# touchy_feely.net
KiCad netlist of a schematic drawn in EAGLE
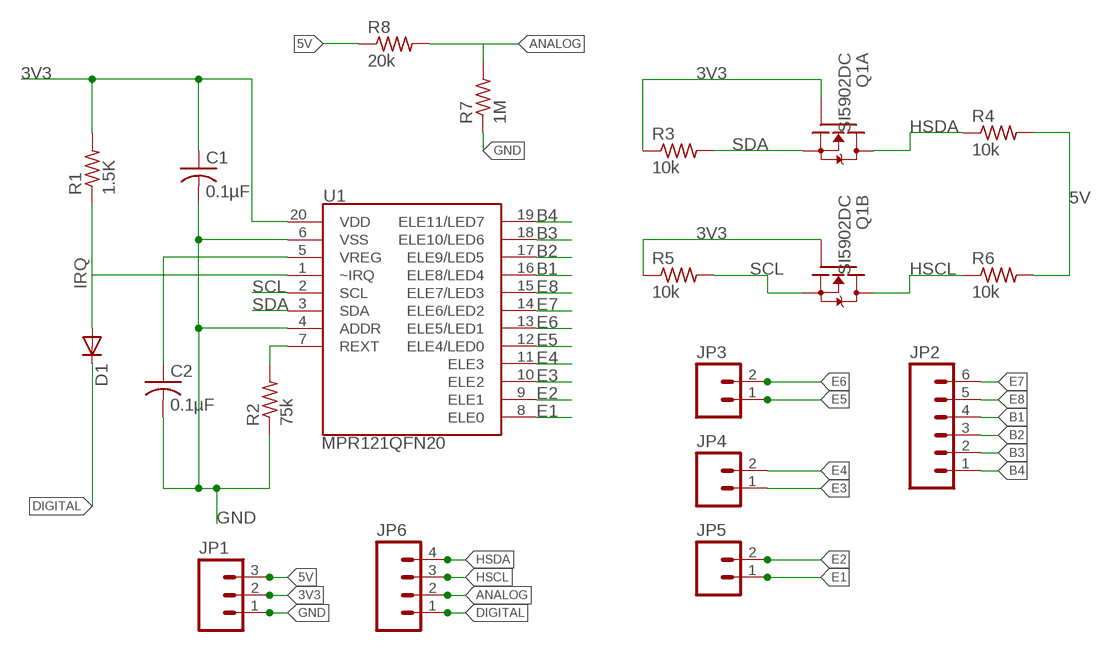
[diagram p0: schematic, sheet 1]

(export (version "E")
  (design (tool "Eeschema 10.0.6"))
  (components
    (comp (ref "C1")
      (value "0.1µF")
      (footprint "eagle-import:C0603K")
      (libsource (lib "eagle-import") (part "C-USC0603K"))
    )
    (comp (ref "C2")
      (value "0.1µF")
      (footprint "eagle-import:C0603K")
      (libsource (lib "eagle-import") (part "C-USC0603K"))
    )
    (comp (ref "D1")
      (value "DIODE-MINIMELF")
      (footprint "eagle-import:MINIMELF")
      (libsource (lib "eagle-import") (part "DIODE-MINIMELF"))
    )
    (comp (ref "JP1")
      (value "M03PTH")
      (footprint "eagle-import:1X03")
      (libsource (lib "eagle-import") (part "M03PTH"))
    )
    (comp (ref "JP2")
      (value "M06SIP")
      (footprint "eagle-import:1X06")
      (libsource (lib "eagle-import") (part "M06SIP"))
    )
    (comp (ref "JP3")
      (value "M023.5MM")
      (footprint "eagle-import:SCREWTERMINAL-3.5MM-2")
      (libsource (lib "eagle-import") (part "M023.5MM"))
    )
    (comp (ref "JP4")
      (value "M023.5MM")
      (footprint "eagle-import:SCREWTERMINAL-3.5MM-2")
      (libsource (lib "eagle-import") (part "M023.5MM"))
    )
    (comp (ref "JP5")
      (value "M023.5MM")
      (footprint "eagle-import:SCREWTERMINAL-3.5MM-2")
      (libsource (lib "eagle-import") (part "M023.5MM"))
    )
    (comp (ref "JP6")
      (value "M04PTH")
      (footprint "eagle-import:1X04")
      (libsource (lib "eagle-import") (part "M04PTH"))
    )
    (comp (ref "Q1")
      (value "SI5902DC")
      (footprint "eagle-import:1206-8CHIP-FET")
      (libsource (lib "eagle-import") (part "SI5902DC"))
    )
    (comp (ref "R1")
      (value "1.5K")
      (footprint "eagle-import:M0805")
      (libsource (lib "eagle-import") (part "resistor_R-US_M0805"))
    )
    (comp (ref "R2")
      (value "75k")
      (footprint "eagle-import:M0805")
      (libsource (lib "eagle-import") (part "resistor_R-US_M0805"))
    )
    (comp (ref "R3")
      (value "10k")
      (footprint "eagle-import:M0805")
      (libsource (lib "eagle-import") (part "resistor_R-US_M0805"))
    )
    (comp (ref "R4")
      (value "10k")
      (footprint "eagle-import:M0805")
      (libsource (lib "eagle-import") (part "resistor_R-US_M0805"))
    )
    (comp (ref "R5")
      (value "10k")
      (footprint "eagle-import:M0805")
      (libsource (lib "eagle-import") (part "resistor_R-US_M0805"))
    )
    (comp (ref "R6")
      (value "10k")
      (footprint "eagle-import:M0805")
      (libsource (lib "eagle-import") (part "resistor_R-US_M0805"))
    )
    (comp (ref "R7")
      (value "1M")
      (footprint "eagle-import:R0805")
      (libsource (lib "eagle-import") (part "R-US_R0805"))
    )
    (comp (ref "R8")
      (value "20k")
      (footprint "eagle-import:R0805")
      (libsource (lib "eagle-import") (part "R-US_R0805"))
    )
    (comp (ref "U1")
      (value "MPR121QFN20")
      (footprint "eagle-import:QFN-20-0.4MM")
      (libsource (lib "eagle-import") (part "MPR121QFN20"))
    )
  )
  (nets
    (net (code "1") (name "/IRQ") (class "Default")
      (node (ref "D1") (pin "A") (pinfunction "A_A") (pintype "passive"))
      (node (ref "R1") (pin "1") (pinfunction "1_1") (pintype "passive"))
      (node (ref "U1") (pin "1") (pinfunction "~{IRQ}_1") (pintype "bidirectional"))
    )
    (net (code "2") (name "/SCL") (class "Default")
      (node (ref "Q1") (pin "3") (pinfunction "S_3") (pintype "passive"))
      (node (ref "R5") (pin "2") (pinfunction "2_2") (pintype "passive"))
      (node (ref "U1") (pin "2") (pinfunction "SCL_2") (pintype "bidirectional"))
    )
    (net (code "3") (name "/SDA") (class "Default")
      (node (ref "Q1") (pin "1") (pinfunction "S_1") (pintype "passive"))
      (node (ref "R3") (pin "2") (pinfunction "2_2") (pintype "passive"))
      (node (ref "U1") (pin "3") (pinfunction "SDA_3") (pintype "bidirectional"))
    )
    (net (code "4") (name "3V3") (class "Default")
      (node (ref "C1") (pin "1") (pinfunction "1_1") (pintype "passive"))
      (node (ref "JP1") (pin "2") (pinfunction "2_2") (pintype "passive"))
      (node (ref "Q1") (pin "2") (pinfunction "G_2") (pintype "passive"))
      (node (ref "Q1") (pin "4") (pinfunction "G_4") (pintype "passive"))
      (node (ref "R1") (pin "2") (pinfunction "2_2") (pintype "passive"))
      (node (ref "R3") (pin "1") (pinfunction "1_1") (pintype "passive"))
      (node (ref "R5") (pin "1") (pinfunction "1_1") (pintype "passive"))
      (node (ref "U1") (pin "20") (pinfunction "VDD_20") (pintype "bidirectional"))
    )
    (net (code "5") (name "5V") (class "Default")
      (node (ref "JP1") (pin "3") (pinfunction "3_3") (pintype "passive"))
      (node (ref "R4") (pin "2") (pinfunction "2_2") (pintype "passive"))
      (node (ref "R6") (pin "2") (pinfunction "2_2") (pintype "passive"))
      (node (ref "R8") (pin "1") (pinfunction "1_1") (pintype "passive"))
    )
    (net (code "6") (name "ANALOG") (class "Default")
      (node (ref "JP6") (pin "2") (pinfunction "2_2") (pintype "passive"))
      (node (ref "R7") (pin "2") (pinfunction "2_2") (pintype "passive"))
      (node (ref "R8") (pin "2") (pinfunction "2_2") (pintype "passive"))
    )
    (net (code "7") (name "B1") (class "Default")
      (node (ref "JP2") (pin "4") (pinfunction "4_4") (pintype "passive"))
      (node (ref "U1") (pin "16") (pinfunction "ELE8/LED4_16") (pintype "bidirectional"))
    )
    (net (code "8") (name "B2") (class "Default")
      (node (ref "JP2") (pin "3") (pinfunction "3_3") (pintype "passive"))
      (node (ref "U1") (pin "17") (pinfunction "ELE9/LED5_17") (pintype "bidirectional"))
    )
    (net (code "9") (name "B3") (class "Default")
      (node (ref "JP2") (pin "2") (pinfunction "2_2") (pintype "passive"))
      (node (ref "U1") (pin "18") (pinfunction "ELE10/LED6_18") (pintype "bidirectional"))
    )
    (net (code "10") (name "B4") (class "Default")
      (node (ref "JP2") (pin "1") (pinfunction "1_1") (pintype "passive"))
      (node (ref "U1") (pin "19") (pinfunction "ELE11/LED7_19") (pintype "bidirectional"))
    )
    (net (code "11") (name "DIGITAL") (class "Default")
      (node (ref "D1") (pin "C") (pinfunction "C_C") (pintype "passive"))
      (node (ref "JP6") (pin "1") (pinfunction "1_1") (pintype "passive"))
    )
    (net (code "12") (name "E1") (class "Default")
      (node (ref "JP5") (pin "1") (pinfunction "1_1") (pintype "passive"))
      (node (ref "U1") (pin "8") (pinfunction "ELE0_8") (pintype "bidirectional"))
    )
    (net (code "13") (name "E2") (class "Default")
      (node (ref "JP5") (pin "2") (pinfunction "2_2") (pintype "passive"))
      (node (ref "U1") (pin "9") (pinfunction "ELE1_9") (pintype "bidirectional"))
    )
    (net (code "14") (name "E3") (class "Default")
      (node (ref "JP4") (pin "1") (pinfunction "1_1") (pintype "passive"))
      (node (ref "U1") (pin "10") (pinfunction "ELE2_10") (pintype "bidirectional"))
    )
    (net (code "15") (name "E4") (class "Default")
      (node (ref "JP4") (pin "2") (pinfunction "2_2") (pintype "passive"))
      (node (ref "U1") (pin "11") (pinfunction "ELE3_11") (pintype "bidirectional"))
    )
    (net (code "16") (name "E5") (class "Default")
      (node (ref "JP3") (pin "1") (pinfunction "1_1") (pintype "passive"))
      (node (ref "U1") (pin "12") (pinfunction "ELE4/LED0_12") (pintype "bidirectional"))
    )
    (net (code "17") (name "E6") (class "Default")
      (node (ref "JP3") (pin "2") (pinfunction "2_2") (pintype "passive"))
      (node (ref "U1") (pin "13") (pinfunction "ELE5/LED1_13") (pintype "bidirectional"))
    )
    (net (code "18") (name "E7") (class "Default")
      (node (ref "JP2") (pin "6") (pinfunction "6_6") (pintype "passive"))
      (node (ref "U1") (pin "14") (pinfunction "ELE6/LED2_14") (pintype "bidirectional"))
    )
    (net (code "19") (name "E8") (class "Default")
      (node (ref "JP2") (pin "5") (pinfunction "5_5") (pintype "passive"))
      (node (ref "U1") (pin "15") (pinfunction "ELE7/LED3_15") (pintype "bidirectional"))
    )
    (net (code "20") (name "GND") (class "Default")
      (node (ref "C1") (pin "2") (pinfunction "2_2") (pintype "passive"))
      (node (ref "C2") (pin "2") (pinfunction "2_2") (pintype "passive"))
      (node (ref "JP1") (pin "1") (pinfunction "1_1") (pintype "passive"))
      (node (ref "R2") (pin "1") (pinfunction "1_1") (pintype "passive"))
      (node (ref "R7") (pin "1") (pinfunction "1_1") (pintype "passive"))
      (node (ref "U1") (pin "4") (pinfunction "ADDR_4") (pintype "bidirectional"))
      (node (ref "U1") (pin "6") (pinfunction "VSS_6") (pintype "bidirectional"))
    )
    (net (code "21") (name "HSCL") (class "Default")
      (node (ref "JP6") (pin "3") (pinfunction "3_3") (pintype "passive"))
      (node (ref "Q1") (pin "5") (pinfunction "D_5") (pintype "passive"))
      (node (ref "Q1") (pin "6") (pinfunction "D_6") (pintype "passive"))
      (node (ref "R6") (pin "1") (pinfunction "1_1") (pintype "passive"))
    )
    (net (code "22") (name "HSDA") (class "Default")
      (node (ref "JP6") (pin "4") (pinfunction "4_4") (pintype "passive"))
      (node (ref "Q1") (pin "7") (pinfunction "D_7") (pintype "passive"))
      (node (ref "Q1") (pin "8") (pinfunction "D_8") (pintype "passive"))
      (node (ref "R4") (pin "1") (pinfunction "1_1") (pintype "passive"))
    )
    (net (code "23") (name "Net-(U1-REXT)") (class "Default")
      (node (ref "R2") (pin "2") (pinfunction "2_2") (pintype "passive"))
      (node (ref "U1") (pin "7") (pinfunction "REXT_7") (pintype "bidirectional"))
    )
    (net (code "24") (name "Net-(U1-VREG)") (class "Default")
      (node (ref "C2") (pin "1") (pinfunction "1_1") (pintype "passive"))
      (node (ref "U1") (pin "5") (pinfunction "VREG_5") (pintype "bidirectional"))
    )
  )
)
